# R3-URC18-4-002-002.net
KiCad netlist of a schematic drawn in EAGLE
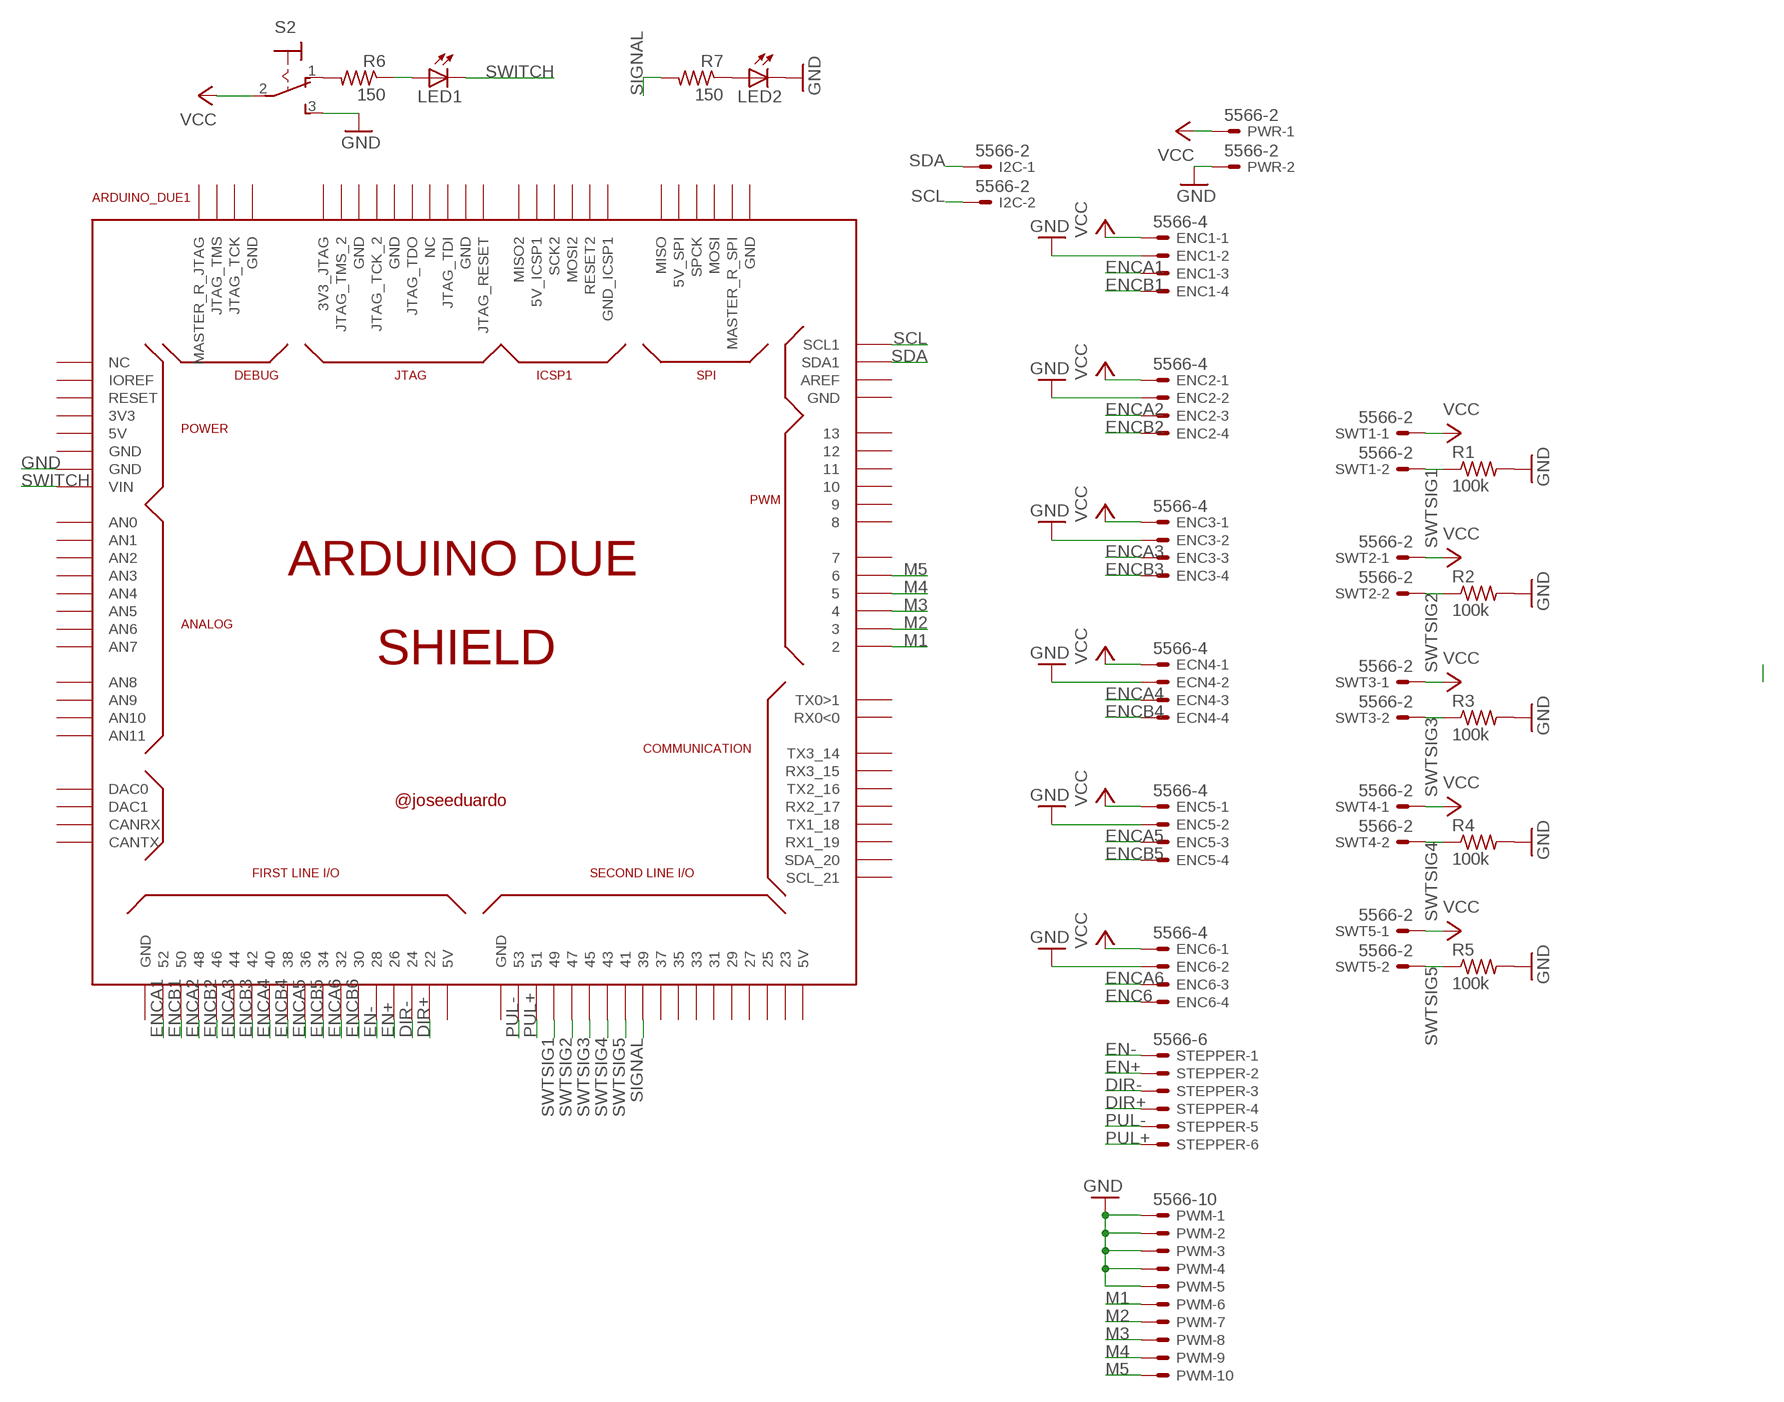
[diagram p0: schematic, sheet 1]

(export (version "E")
  (design (tool "Eeschema 10.0.6"))
  (components
    (comp (ref "ARDUINO_DUE1")
      (value "ARDUINO_DUE_SHIELD")
      (footprint "eagle-import:ARDUINO_DUE_SHIELD")
      (libsource (lib "eagle-import") (part "ARDUINO_DUE_SHIELD"))
    )
    (comp (ref "ECN4")
      (value "5566-4")
      (footprint "eagle-import:5566-4")
      (libsource (lib "eagle-import") (part "5566-4"))
    )
    (comp (ref "ENC1")
      (value "5566-4")
      (footprint "eagle-import:5566-4")
      (libsource (lib "eagle-import") (part "5566-4"))
    )
    (comp (ref "ENC2")
      (value "5566-4")
      (footprint "eagle-import:5566-4")
      (libsource (lib "eagle-import") (part "5566-4"))
    )
    (comp (ref "ENC3")
      (value "5566-4")
      (footprint "eagle-import:5566-4")
      (libsource (lib "eagle-import") (part "5566-4"))
    )
    (comp (ref "ENC5")
      (value "5566-4")
      (footprint "eagle-import:5566-4")
      (libsource (lib "eagle-import") (part "5566-4"))
    )
    (comp (ref "ENC6")
      (value "5566-4")
      (footprint "eagle-import:5566-4")
      (libsource (lib "eagle-import") (part "5566-4"))
    )
    (comp (ref "I2C")
      (value "5566-2")
      (footprint "eagle-import:5566-2")
      (libsource (lib "eagle-import") (part "5566-2"))
    )
    (comp (ref "LED1")
      (value "LED5MM")
      (footprint "eagle-import:LED5MM")
      (libsource (lib "eagle-import") (part "LED5MM"))
    )
    (comp (ref "LED2")
      (value "LED5MM")
      (footprint "eagle-import:LED5MM")
      (libsource (lib "eagle-import") (part "LED5MM"))
    )
    (comp (ref "PWM")
      (value "5566-10")
      (footprint "eagle-import:5566-10")
      (libsource (lib "eagle-import") (part "5566-10"))
    )
    (comp (ref "PWR")
      (value "5566-2")
      (footprint "eagle-import:5566-2")
      (libsource (lib "eagle-import") (part "5566-2"))
    )
    (comp (ref "R1")
      (value "100k")
      (footprint "eagle-import:0207_10")
      (libsource (lib "eagle-import") (part "R-US_0207/10"))
    )
    (comp (ref "R2")
      (value "100k")
      (footprint "eagle-import:0207_10")
      (libsource (lib "eagle-import") (part "R-US_0207/10"))
    )
    (comp (ref "R3")
      (value "100k")
      (footprint "eagle-import:0207_10")
      (libsource (lib "eagle-import") (part "R-US_0207/10"))
    )
    (comp (ref "R4")
      (value "100k")
      (footprint "eagle-import:0207_10")
      (libsource (lib "eagle-import") (part "R-US_0207/10"))
    )
    (comp (ref "R5")
      (value "100k")
      (footprint "eagle-import:0207_10")
      (libsource (lib "eagle-import") (part "R-US_0207/10"))
    )
    (comp (ref "R6")
      (value "150")
      (footprint "eagle-import:0207_10")
      (libsource (lib "eagle-import") (part "R-US_0207/10"))
    )
    (comp (ref "R7")
      (value "150")
      (footprint "eagle-import:0207_10")
      (libsource (lib "eagle-import") (part "R-US_0207/10"))
    )
    (comp (ref "S2")
      (value "M9040P")
      (footprint "eagle-import:M9040P")
      (libsource (lib "eagle-import") (part "M9040P"))
    )
    (comp (ref "STEPPER")
      (value "5566-6")
      (footprint "eagle-import:5566-6")
      (fields (field (name "MPN") "95566-61002"))
      (libsource (lib "eagle-import") (part "5566-6"))
    )
    (comp (ref "SWT1")
      (value "5566-2")
      (footprint "eagle-import:5566-2")
      (libsource (lib "eagle-import") (part "5566-2"))
    )
    (comp (ref "SWT2")
      (value "5566-2")
      (footprint "eagle-import:5566-2")
      (libsource (lib "eagle-import") (part "5566-2"))
    )
    (comp (ref "SWT3")
      (value "5566-2")
      (footprint "eagle-import:5566-2")
      (libsource (lib "eagle-import") (part "5566-2"))
    )
    (comp (ref "SWT4")
      (value "5566-2")
      (footprint "eagle-import:5566-2")
      (libsource (lib "eagle-import") (part "5566-2"))
    )
    (comp (ref "SWT5")
      (value "5566-2")
      (footprint "eagle-import:5566-2")
      (libsource (lib "eagle-import") (part "5566-2"))
    )
  )
  (nets
    (net (code "1") (name "/DIR+") (class "Default")
      (node (ref "ARDUINO_DUE1") (pin "22") (pinfunction "22_22") (pintype "bidirectional"))
      (node (ref "STEPPER") (pin "4") (pinfunction "S_4") (pintype "passive"))
    )
    (net (code "2") (name "/DIR-") (class "Default")
      (node (ref "ARDUINO_DUE1") (pin "24") (pinfunction "24_24") (pintype "bidirectional"))
      (node (ref "STEPPER") (pin "3") (pinfunction "S_3") (pintype "passive"))
    )
    (net (code "3") (name "/EN+") (class "Default")
      (node (ref "ARDUINO_DUE1") (pin "26") (pinfunction "26_26") (pintype "bidirectional"))
      (node (ref "STEPPER") (pin "2") (pinfunction "S_2") (pintype "passive"))
    )
    (net (code "4") (name "/EN-") (class "Default")
      (node (ref "ARDUINO_DUE1") (pin "28") (pinfunction "28_28") (pintype "bidirectional"))
      (node (ref "STEPPER") (pin "1") (pinfunction "S_1") (pintype "passive"))
    )
    (net (code "5") (name "/ENC6") (class "Default")
      (node (ref "ENC6") (pin "4") (pinfunction "S_4") (pintype "passive"))
    )
    (net (code "6") (name "/ENCA1") (class "Default")
      (node (ref "ARDUINO_DUE1") (pin "52") (pinfunction "52_52") (pintype "bidirectional"))
      (node (ref "ENC1") (pin "3") (pinfunction "S_3") (pintype "passive"))
    )
    (net (code "7") (name "/ENCA2") (class "Default")
      (node (ref "ARDUINO_DUE1") (pin "48") (pinfunction "48_48") (pintype "bidirectional"))
      (node (ref "ENC2") (pin "3") (pinfunction "S_3") (pintype "passive"))
    )
    (net (code "8") (name "/ENCA3") (class "Default")
      (node (ref "ARDUINO_DUE1") (pin "44") (pinfunction "44_44") (pintype "bidirectional"))
      (node (ref "ENC3") (pin "3") (pinfunction "S_3") (pintype "passive"))
    )
    (net (code "9") (name "/ENCA4") (class "Default")
      (node (ref "ARDUINO_DUE1") (pin "40") (pinfunction "40_40") (pintype "bidirectional"))
      (node (ref "ECN4") (pin "3") (pinfunction "S_3") (pintype "passive"))
    )
    (net (code "10") (name "/ENCA5") (class "Default")
      (node (ref "ARDUINO_DUE1") (pin "36") (pinfunction "36_36") (pintype "bidirectional"))
      (node (ref "ENC5") (pin "3") (pinfunction "S_3") (pintype "passive"))
    )
    (net (code "11") (name "/ENCA6") (class "Default")
      (node (ref "ARDUINO_DUE1") (pin "32") (pinfunction "32_32") (pintype "bidirectional"))
      (node (ref "ENC6") (pin "3") (pinfunction "S_3") (pintype "passive"))
    )
    (net (code "12") (name "/ENCB1") (class "Default")
      (node (ref "ARDUINO_DUE1") (pin "50") (pinfunction "50_50") (pintype "bidirectional"))
      (node (ref "ENC1") (pin "4") (pinfunction "S_4") (pintype "passive"))
    )
    (net (code "13") (name "/ENCB2") (class "Default")
      (node (ref "ARDUINO_DUE1") (pin "46") (pinfunction "46_46") (pintype "bidirectional"))
      (node (ref "ENC2") (pin "4") (pinfunction "S_4") (pintype "passive"))
    )
    (net (code "14") (name "/ENCB3") (class "Default")
      (node (ref "ARDUINO_DUE1") (pin "42") (pinfunction "42_42") (pintype "bidirectional"))
      (node (ref "ENC3") (pin "4") (pinfunction "S_4") (pintype "passive"))
    )
    (net (code "15") (name "/ENCB4") (class "Default")
      (node (ref "ARDUINO_DUE1") (pin "38") (pinfunction "38_38") (pintype "bidirectional"))
      (node (ref "ECN4") (pin "4") (pinfunction "S_4") (pintype "passive"))
    )
    (net (code "16") (name "/ENCB5") (class "Default")
      (node (ref "ARDUINO_DUE1") (pin "34") (pinfunction "34_34") (pintype "bidirectional"))
      (node (ref "ENC5") (pin "4") (pinfunction "S_4") (pintype "passive"))
    )
    (net (code "17") (name "/ENCB6") (class "Default")
      (node (ref "ARDUINO_DUE1") (pin "30") (pinfunction "30_30") (pintype "bidirectional"))
    )
    (net (code "18") (name "/M1") (class "Default")
      (node (ref "ARDUINO_DUE1") (pin "2") (pinfunction "2_2") (pintype "bidirectional"))
      (node (ref "PWM") (pin "6") (pinfunction "S_6") (pintype "passive"))
    )
    (net (code "19") (name "/M2") (class "Default")
      (node (ref "ARDUINO_DUE1") (pin "3") (pinfunction "3_3") (pintype "bidirectional"))
      (node (ref "PWM") (pin "7") (pinfunction "S_7") (pintype "passive"))
    )
    (net (code "20") (name "/M3") (class "Default")
      (node (ref "ARDUINO_DUE1") (pin "4") (pinfunction "4_4") (pintype "bidirectional"))
      (node (ref "PWM") (pin "8") (pinfunction "S_8") (pintype "passive"))
    )
    (net (code "21") (name "/M4") (class "Default")
      (node (ref "ARDUINO_DUE1") (pin "5") (pinfunction "5_5") (pintype "bidirectional"))
      (node (ref "PWM") (pin "9") (pinfunction "S_9") (pintype "passive"))
    )
    (net (code "22") (name "/M5") (class "Default")
      (node (ref "ARDUINO_DUE1") (pin "6") (pinfunction "6_6") (pintype "bidirectional"))
      (node (ref "PWM") (pin "10") (pinfunction "S_10") (pintype "passive"))
    )
    (net (code "23") (name "/PUL+") (class "Default")
      (node (ref "ARDUINO_DUE1") (pin "51") (pinfunction "51_51") (pintype "bidirectional"))
      (node (ref "STEPPER") (pin "6") (pinfunction "S_6") (pintype "passive"))
    )
    (net (code "24") (name "/PUL-") (class "Default")
      (node (ref "ARDUINO_DUE1") (pin "53") (pinfunction "53_53") (pintype "bidirectional"))
      (node (ref "STEPPER") (pin "5") (pinfunction "S_5") (pintype "passive"))
    )
    (net (code "25") (name "/SCL") (class "Default")
      (node (ref "ARDUINO_DUE1") (pin "SCL1") (pinfunction "SCL1_SCL1") (pintype "bidirectional"))
      (node (ref "I2C") (pin "2") (pinfunction "S_2") (pintype "passive"))
    )
    (net (code "26") (name "/SDA") (class "Default")
      (node (ref "ARDUINO_DUE1") (pin "SDA1") (pinfunction "SDA1_SDA1") (pintype "bidirectional"))
      (node (ref "I2C") (pin "1") (pinfunction "S_1") (pintype "passive"))
    )
    (net (code "27") (name "/SIGNAL") (class "Default")
      (node (ref "ARDUINO_DUE1") (pin "39") (pinfunction "39_39") (pintype "bidirectional"))
      (node (ref "R7") (pin "2") (pinfunction "2_2") (pintype "passive"))
    )
    (net (code "28") (name "/SWITCH") (class "Default")
      (node (ref "ARDUINO_DUE1") (pin "VIN") (pinfunction "VIN_VIN") (pintype "bidirectional"))
      (node (ref "LED1") (pin "K") (pinfunction "C_K") (pintype "passive"))
    )
    (net (code "29") (name "/SWTSIG1") (class "Default")
      (node (ref "ARDUINO_DUE1") (pin "49") (pinfunction "49_49") (pintype "bidirectional"))
      (node (ref "R1") (pin "1") (pinfunction "1_1") (pintype "passive"))
      (node (ref "SWT1") (pin "2") (pinfunction "S_2") (pintype "passive"))
    )
    (net (code "30") (name "/SWTSIG2") (class "Default")
      (node (ref "ARDUINO_DUE1") (pin "47") (pinfunction "47_47") (pintype "bidirectional"))
      (node (ref "R2") (pin "1") (pinfunction "1_1") (pintype "passive"))
      (node (ref "SWT2") (pin "2") (pinfunction "S_2") (pintype "passive"))
    )
    (net (code "31") (name "/SWTSIG3") (class "Default")
      (node (ref "ARDUINO_DUE1") (pin "45") (pinfunction "45_45") (pintype "bidirectional"))
      (node (ref "R3") (pin "1") (pinfunction "1_1") (pintype "passive"))
      (node (ref "SWT3") (pin "2") (pinfunction "S_2") (pintype "passive"))
    )
    (net (code "32") (name "/SWTSIG4") (class "Default")
      (node (ref "ARDUINO_DUE1") (pin "43") (pinfunction "43_43") (pintype "bidirectional"))
      (node (ref "R4") (pin "1") (pinfunction "1_1") (pintype "passive"))
      (node (ref "SWT4") (pin "2") (pinfunction "S_2") (pintype "passive"))
    )
    (net (code "33") (name "/SWTSIG5") (class "Default")
      (node (ref "ARDUINO_DUE1") (pin "41") (pinfunction "41_41") (pintype "bidirectional"))
      (node (ref "R5") (pin "1") (pinfunction "1_1") (pintype "passive"))
      (node (ref "SWT5") (pin "2") (pinfunction "S_2") (pintype "passive"))
    )
    (net (code "34") (name "GND") (class "Default")
      (node (ref "ARDUINO_DUE1") (pin "GND_1") (pinfunction "GND_GND_1") (pintype "bidirectional"))
      (node (ref "ECN4") (pin "2") (pinfunction "S_2") (pintype "passive"))
      (node (ref "ENC1") (pin "2") (pinfunction "S_2") (pintype "passive"))
      (node (ref "ENC2") (pin "2") (pinfunction "S_2") (pintype "passive"))
      (node (ref "ENC3") (pin "2") (pinfunction "S_2") (pintype "passive"))
      (node (ref "ENC5") (pin "2") (pinfunction "S_2") (pintype "passive"))
      (node (ref "ENC6") (pin "2") (pinfunction "S_2") (pintype "passive"))
      (node (ref "LED2") (pin "K") (pinfunction "C_K") (pintype "passive"))
      (node (ref "PWM") (pin "1") (pinfunction "S_1") (pintype "passive"))
      (node (ref "PWM") (pin "2") (pinfunction "S_2") (pintype "passive"))
      (node (ref "PWM") (pin "3") (pinfunction "S_3") (pintype "passive"))
      (node (ref "PWM") (pin "4") (pinfunction "S_4") (pintype "passive"))
      (node (ref "PWM") (pin "5") (pinfunction "S_5") (pintype "passive"))
      (node (ref "PWR") (pin "2") (pinfunction "S_2") (pintype "passive"))
      (node (ref "R1") (pin "2") (pinfunction "2_2") (pintype "passive"))
      (node (ref "R2") (pin "2") (pinfunction "2_2") (pintype "passive"))
      (node (ref "R3") (pin "2") (pinfunction "2_2") (pintype "passive"))
      (node (ref "R4") (pin "2") (pinfunction "2_2") (pintype "passive"))
      (node (ref "R5") (pin "2") (pinfunction "2_2") (pintype "passive"))
      (node (ref "S2") (pin "3") (pinfunction "S_3") (pintype "passive"))
    )
    (net (code "35") (name "Net-(LED1-PadA)") (class "Default")
      (node (ref "LED1") (pin "A") (pinfunction "A_A") (pintype "passive"))
      (node (ref "R6") (pin "1") (pinfunction "1_1") (pintype "passive"))
    )
    (net (code "36") (name "Net-(LED2-PadA)") (class "Default")
      (node (ref "LED2") (pin "A") (pinfunction "A_A") (pintype "passive"))
      (node (ref "R7") (pin "1") (pinfunction "1_1") (pintype "passive"))
    )
    (net (code "37") (name "Net-(S2-O)") (class "Default")
      (node (ref "R6") (pin "2") (pinfunction "2_2") (pintype "passive"))
      (node (ref "S2") (pin "1") (pinfunction "O_1") (pintype "passive"))
    )
    (net (code "38") (name "VCC") (class "Default")
      (node (ref "ECN4") (pin "1") (pinfunction "S_1") (pintype "passive"))
      (node (ref "ENC1") (pin "1") (pinfunction "S_1") (pintype "passive"))
      (node (ref "ENC2") (pin "1") (pinfunction "S_1") (pintype "passive"))
      (node (ref "ENC3") (pin "1") (pinfunction "S_1") (pintype "passive"))
      (node (ref "ENC5") (pin "1") (pinfunction "S_1") (pintype "passive"))
      (node (ref "ENC6") (pin "1") (pinfunction "S_1") (pintype "passive"))
      (node (ref "PWR") (pin "1") (pinfunction "S_1") (pintype "passive"))
      (node (ref "S2") (pin "2") (pinfunction "P_2") (pintype "passive"))
      (node (ref "SWT1") (pin "1") (pinfunction "S_1") (pintype "passive"))
      (node (ref "SWT2") (pin "1") (pinfunction "S_1") (pintype "passive"))
      (node (ref "SWT3") (pin "1") (pinfunction "S_1") (pintype "passive"))
      (node (ref "SWT4") (pin "1") (pinfunction "S_1") (pintype "passive"))
      (node (ref "SWT5") (pin "1") (pinfunction "S_1") (pintype "passive"))
    )
    (net (code "39") (name "unconnected-(ARDUINO_DUE1-5V-Pad5V0)") (class "Default")
      (node (ref "ARDUINO_DUE1") (pin "5V0") (pinfunction "5V_5V0") (pintype "bidirectional"))
    )
    (net (code "40") (name "unconnected-(ARDUINO_DUE1-5V-Pad5V0_1)") (class "Default")
      (node (ref "ARDUINO_DUE1") (pin "5V0_1") (pinfunction "5V_5V0_1") (pintype "bidirectional"))
    )
    (net (code "41") (name "unconnected-(ARDUINO_DUE1-5V-Pad5V0_2)") (class "Default")
      (node (ref "ARDUINO_DUE1") (pin "5V0_2") (pinfunction "5V_5V0_2") (pintype "bidirectional"))
    )
    (net (code "42") (name "unconnected-(ARDUINO_DUE1-5V_SPI-Pad5V_2)") (class "Default")
      (node (ref "ARDUINO_DUE1") (pin "5V_2") (pinfunction "5V_SPI_5V_2") (pintype "bidirectional"))
    )
    (net (code "43") (name "unconnected-(ARDUINO_DUE1-AN0-PadA0)") (class "Default")
      (node (ref "ARDUINO_DUE1") (pin "A0") (pinfunction "AN0_A0") (pintype "bidirectional"))
    )
    (net (code "44") (name "unconnected-(ARDUINO_DUE1-AN1-PadA1)") (class "Default")
      (node (ref "ARDUINO_DUE1") (pin "A1") (pinfunction "AN1_A1") (pintype "bidirectional"))
    )
    (net (code "45") (name "unconnected-(ARDUINO_DUE1-AN2-PadA2)") (class "Default")
      (node (ref "ARDUINO_DUE1") (pin "A2") (pinfunction "AN2_A2") (pintype "bidirectional"))
    )
    (net (code "46") (name "unconnected-(ARDUINO_DUE1-AN3-PadA3)") (class "Default")
      (node (ref "ARDUINO_DUE1") (pin "A3") (pinfunction "AN3_A3") (pintype "bidirectional"))
    )
    (net (code "47") (name "unconnected-(ARDUINO_DUE1-AN4-PadA4)") (class "Default")
      (node (ref "ARDUINO_DUE1") (pin "A4") (pinfunction "AN4_A4") (pintype "bidirectional"))
    )
    (net (code "48") (name "unconnected-(ARDUINO_DUE1-AN5-PadA5)") (class "Default")
      (node (ref "ARDUINO_DUE1") (pin "A5") (pinfunction "AN5_A5") (pintype "bidirectional"))
    )
    (net (code "49") (name "unconnected-(ARDUINO_DUE1-AN6-PadA6)") (class "Default")
      (node (ref "ARDUINO_DUE1") (pin "A6") (pinfunction "AN6_A6") (pintype "bidirectional"))
    )
    (net (code "50") (name "unconnected-(ARDUINO_DUE1-AN7-PadA7)") (class "Default")
      (node (ref "ARDUINO_DUE1") (pin "A7") (pinfunction "AN7_A7") (pintype "bidirectional"))
    )
    (net (code "51") (name "unconnected-(ARDUINO_DUE1-AN8-PadA8)") (class "Default")
      (node (ref "ARDUINO_DUE1") (pin "A8") (pinfunction "AN8_A8") (pintype "bidirectional"))
    )
    (net (code "52") (name "unconnected-(ARDUINO_DUE1-AN9-PadA9)") (class "Default")
      (node (ref "ARDUINO_DUE1") (pin "A9") (pinfunction "AN9_A9") (pintype "bidirectional"))
    )
    (net (code "53") (name "unconnected-(ARDUINO_DUE1-AN10-PadA10)") (class "Default")
      (node (ref "ARDUINO_DUE1") (pin "A10") (pinfunction "AN10_A10") (pintype "bidirectional"))
    )
    (net (code "54") (name "unconnected-(ARDUINO_DUE1-AN11-PadA11)") (class "Default")
      (node (ref "ARDUINO_DUE1") (pin "A11") (pinfunction "AN11_A11") (pintype "bidirectional"))
    )
    (net (code "55") (name "unconnected-(ARDUINO_DUE1-GND-PadGND_2)") (class "Default")
      (node (ref "ARDUINO_DUE1") (pin "GND_2") (pinfunction "GND_GND_2") (pintype "bidirectional"))
    )
    (net (code "56") (name "unconnected-(ARDUINO_DUE1-GND-PadGND_3)") (class "Default")
      (node (ref "ARDUINO_DUE1") (pin "GND_3") (pinfunction "GND_GND_3") (pintype "bidirectional"))
    )
    (net (code "57") (name "unconnected-(ARDUINO_DUE1-GND-PadGND_4)") (class "Default")
      (node (ref "ARDUINO_DUE1") (pin "GND_4") (pinfunction "GND_GND_4") (pintype "bidirectional"))
    )
    (net (code "58") (name "unconnected-(ARDUINO_DUE1-GND-PadGND_5)") (class "Default")
      (node (ref "ARDUINO_DUE1") (pin "GND_5") (pinfunction "GND_GND_5") (pintype "bidirectional"))
    )
    (net (code "59") (name "unconnected-(ARDUINO_DUE1-GND-PadGND_7)") (class "Default")
      (node (ref "ARDUINO_DUE1") (pin "GND_7") (pinfunction "GND_GND_7") (pintype "bidirectional"))
    )
    (net (code "60") (name "unconnected-(ARDUINO_DUE1-GND-PadGND_8)") (class "Default")
      (node (ref "ARDUINO_DUE1") (pin "GND_8") (pinfunction "GND_GND_8") (pintype "bidirectional"))
    )
    (net (code "61") (name "unconnected-(ARDUINO_DUE1-GND-PadGND_9)") (class "Default")
      (node (ref "ARDUINO_DUE1") (pin "GND_9") (pinfunction "GND_GND_9") (pintype "bidirectional"))
    )
    (net (code "62") (name "unconnected-(ARDUINO_DUE1-GND-PadGND_10)") (class "Default")
      (node (ref "ARDUINO_DUE1") (pin "GND_10") (pinfunction "GND_GND_10") (pintype "bidirectional"))
    )
    (net (code "63") (name "unconnected-(ARDUINO_DUE1-MASTER_R_JTAG-PadMASTER_RESET_JTAG)") (class "Default")
      (node (ref "ARDUINO_DUE1") (pin "MASTER_RESET_JTAG") (pinfunction "MASTER_R_JTAG_MASTER_RESET_JTAG") (pintype "bidirectional"))
    )
    (net (code "64") (name "unconnected-(ARDUINO_DUE1-MASTER_R_SPI-PadMASTER_RESET_SPI)") (class "Default")
      (node (ref "ARDUINO_DUE1") (pin "MASTER_RESET_SPI") (pinfunction "MASTER_R_SPI_MASTER_RESET_SPI") (pintype "bidirectional"))
    )
    (net (code "65") (name "unconnected-(ARDUINO_DUE1-NC-PadNC_2)") (class "Default")
      (node (ref "ARDUINO_DUE1") (pin "NC_2") (pinfunction "NC_NC_2") (pintype "no_connect"))
    )
    (net (code "66") (name "unconnected-(ARDUINO_DUE1-NC-PadNC_5)") (class "Default")
      (node (ref "ARDUINO_DUE1") (pin "NC_5") (pinfunction "NC_NC_5") (pintype "bidirectional"))
    )
    (net (code "67") (name "unconnected-(ARDUINO_DUE1-Pad3V3)") (class "Default")
      (node (ref "ARDUINO_DUE1") (pin "3V3") (pinfunction "3V3_3V3") (pintype "bidirectional"))
    )
    (net (code "68") (name "unconnected-(ARDUINO_DUE1-Pad3V3_JTAG)") (class "Default")
      (node (ref "ARDUINO_DUE1") (pin "3V3_JTAG") (pinfunction "3V3_JTAG_3V3_JTAG") (pintype "bidirectional"))
    )
    (net (code "69") (name "unconnected-(ARDUINO_DUE1-Pad5V_ICSP1)") (class "Default")
      (node (ref "ARDUINO_DUE1") (pin "5V_ICSP1") (pinfunction "5V_ICSP1_5V_ICSP1") (pintype "bidirectional"))
    )
    (net (code "70") (name "unconnected-(ARDUINO_DUE1-Pad7)") (class "Default")
      (node (ref "ARDUINO_DUE1") (pin "7") (pinfunction "7_7") (pintype "bidirectional"))
    )
    (net (code "71") (name "unconnected-(ARDUINO_DUE1-Pad8)") (class "Default")
      (node (ref "ARDUINO_DUE1") (pin "8") (pinfunction "8_8") (pintype "bidirectional"))
    )
    (net (code "72") (name "unconnected-(ARDUINO_DUE1-Pad9)") (class "Default")
      (node (ref "ARDUINO_DUE1") (pin "9") (pinfunction "9_9") (pintype "bidirectional"))
    )
    (net (code "73") (name "unconnected-(ARDUINO_DUE1-Pad10)") (class "Default")
      (node (ref "ARDUINO_DUE1") (pin "10") (pinfunction "10_10") (pintype "bidirectional"))
    )
    (net (code "74") (name "unconnected-(ARDUINO_DUE1-Pad11)") (class "Default")
      (node (ref "ARDUINO_DUE1") (pin "11") (pinfunction "11_11") (pintype "bidirectional"))
    )
    (net (code "75") (name "unconnected-(ARDUINO_DUE1-Pad12)") (class "Default")
      (node (ref "ARDUINO_DUE1") (pin "12") (pinfunction "12_12") (pintype "bidirectional"))
    )
    (net (code "76") (name "unconnected-(ARDUINO_DUE1-Pad13)") (class "Default")
      (node (ref "ARDUINO_DUE1") (pin "13") (pinfunction "13_13") (pintype "bidirectional"))
    )
    (net (code "77") (name "unconnected-(ARDUINO_DUE1-Pad23)") (class "Default")
      (node (ref "ARDUINO_DUE1") (pin "23") (pinfunction "23_23") (pintype "bidirectional"))
    )
    (net (code "78") (name "unconnected-(ARDUINO_DUE1-Pad25)") (class "Default")
      (node (ref "ARDUINO_DUE1") (pin "25") (pinfunction "25_25") (pintype "bidirectional"))
    )
    (net (code "79") (name "unconnected-(ARDUINO_DUE1-Pad27)") (class "Default")
      (node (ref "ARDUINO_DUE1") (pin "27") (pinfunction "27_27") (pintype "bidirectional"))
    )
    (net (code "80") (name "unconnected-(ARDUINO_DUE1-Pad29)") (class "Default")
      (node (ref "ARDUINO_DUE1") (pin "29") (pinfunction "29_29") (pintype "bidirectional"))
    )
    (net (code "81") (name "unconnected-(ARDUINO_DUE1-Pad31)") (class "Default")
      (node (ref "ARDUINO_DUE1") (pin "31") (pinfunction "31_31") (pintype "bidirectional"))
    )
    (net (code "82") (name "unconnected-(ARDUINO_DUE1-Pad33)") (class "Default")
      (node (ref "ARDUINO_DUE1") (pin "33") (pinfunction "33_33") (pintype "bidirectional"))
    )
    (net (code "83") (name "unconnected-(ARDUINO_DUE1-Pad35)") (class "Default")
      (node (ref "ARDUINO_DUE1") (pin "35") (pinfunction "35_35") (pintype "bidirectional"))
    )
    (net (code "84") (name "unconnected-(ARDUINO_DUE1-Pad37)") (class "Default")
      (node (ref "ARDUINO_DUE1") (pin "37") (pinfunction "37_37") (pintype "bidirectional"))
    )
    (net (code "85") (name "unconnected-(ARDUINO_DUE1-PadAREF)") (class "Default")
      (node (ref "ARDUINO_DUE1") (pin "AREF") (pinfunction "AREF_AREF") (pintype "bidirectional"))
    )
    (net (code "86") (name "unconnected-(ARDUINO_DUE1-PadCANRX)") (class "Default")
      (node (ref "ARDUINO_DUE1") (pin "CANRX") (pinfunction "CANRX_CANRX") (pintype "bidirectional"))
    )
    (net (code "87") (name "unconnected-(ARDUINO_DUE1-PadCANTX)") (class "Default")
      (node (ref "ARDUINO_DUE1") (pin "CANTX") (pinfunction "CANTX_CANTX") (pintype "bidirectional"))
    )
    (net (code "88") (name "unconnected-(ARDUINO_DUE1-PadDAC0)") (class "Default")
      (node (ref "ARDUINO_DUE1") (pin "DAC0") (pinfunction "DAC0_DAC0") (pintype "bidirectional"))
    )
    (net (code "89") (name "unconnected-(ARDUINO_DUE1-PadDAC1)") (class "Default")
      (node (ref "ARDUINO_DUE1") (pin "DAC1") (pinfunction "DAC1_DAC1") (pintype "bidirectional"))
    )
    (net (code "90") (name "unconnected-(ARDUINO_DUE1-PadGND)") (class "Default")
      (node (ref "ARDUINO_DUE1") (pin "GND") (pinfunction "GND_GND") (pintype "bidirectional"))
    )
    (net (code "91") (name "unconnected-(ARDUINO_DUE1-PadGND_ICSP1)") (class "Default")
      (node (ref "ARDUINO_DUE1") (pin "GND_ICSP1") (pinfunction "GND_ICSP1_GND_ICSP1") (pintype "bidirectional"))
    )
    (net (code "92") (name "unconnected-(ARDUINO_DUE1-PadIOREF)") (class "Default")
      (node (ref "ARDUINO_DUE1") (pin "IOREF") (pinfunction "IOREF_IOREF") (pintype "bidirectional"))
    )
    (net (code "93") (name "unconnected-(ARDUINO_DUE1-PadJTAG_RESET)") (class "Default")
      (node (ref "ARDUINO_DUE1") (pin "JTAG_RESET") (pinfunction "JTAG_RESET_JTAG_RESET") (pintype "bidirectional"))
    )
    (net (code "94") (name "unconnected-(ARDUINO_DUE1-PadJTAG_TCK)") (class "Default")
      (node (ref "ARDUINO_DUE1") (pin "JTAG_TCK") (pinfunction "JTAG_TCK_JTAG_TCK") (pintype "bidirectional"))
    )
    (net (code "95") (name "unconnected-(ARDUINO_DUE1-PadJTAG_TCK_2)") (class "Default")
      (node (ref "ARDUINO_DUE1") (pin "JTAG_TCK_2") (pinfunction "JTAG_TCK_2_JTAG_TCK_2") (pintype "bidirectional"))
    )
    (net (code "96") (name "unconnected-(ARDUINO_DUE1-PadJTAG_TDI)") (class "Default")
      (node (ref "ARDUINO_DUE1") (pin "JTAG_TDI") (pinfunction "JTAG_TDI_JTAG_TDI") (pintype "bidirectional"))
    )
    (net (code "97") (name "unconnected-(ARDUINO_DUE1-PadJTAG_TDO)") (class "Default")
      (node (ref "ARDUINO_DUE1") (pin "JTAG_TDO") (pinfunction "JTAG_TDO_JTAG_TDO") (pintype "bidirectional"))
    )
    (net (code "98") (name "unconnected-(ARDUINO_DUE1-PadJTAG_TMS)") (class "Default")
      (node (ref "ARDUINO_DUE1") (pin "JTAG_TMS") (pinfunction "JTAG_TMS_JTAG_TMS") (pintype "bidirectional"))
    )
    (net (code "99") (name "unconnected-(ARDUINO_DUE1-PadJTAG_TMS_2)") (class "Default")
      (node (ref "ARDUINO_DUE1") (pin "JTAG_TMS_2") (pinfunction "JTAG_TMS_2_JTAG_TMS_2") (pintype "bidirectional"))
    )
    (net (code "100") (name "unconnected-(ARDUINO_DUE1-PadMISO)") (class "Default")
      (node (ref "ARDUINO_DUE1") (pin "MISO") (pinfunction "MISO_MISO") (pintype "bidirectional"))
    )
    (net (code "101") (name "unconnected-(ARDUINO_DUE1-PadMISO2)") (class "Default")
      (node (ref "ARDUINO_DUE1") (pin "MISO2") (pinfunction "MISO2_MISO2") (pintype "bidirectional"))
    )
    (net (code "102") (name "unconnected-(ARDUINO_DUE1-PadMOSI)") (class "Default")
      (node (ref "ARDUINO_DUE1") (pin "MOSI") (pinfunction "MOSI_MOSI") (pintype "bidirectional"))
    )
    (net (code "103") (name "unconnected-(ARDUINO_DUE1-PadMOSI2)") (class "Default")
      (node (ref "ARDUINO_DUE1") (pin "MOSI2") (pinfunction "MOSI2_MOSI2") (pintype "bidirectional"))
    )
    (net (code "104") (name "unconnected-(ARDUINO_DUE1-PadRESET)") (class "Default")
      (node (ref "ARDUINO_DUE1") (pin "RESET") (pinfunction "RESET_RESET") (pintype "bidirectional"))
    )
    (net (code "105") (name "unconnected-(ARDUINO_DUE1-PadRESET2)") (class "Default")
      (node (ref "ARDUINO_DUE1") (pin "RESET2") (pinfunction "RESET2_RESET2") (pintype "bidirectional"))
    )
    (net (code "106") (name "unconnected-(ARDUINO_DUE1-PadSCK2)") (class "Default")
      (node (ref "ARDUINO_DUE1") (pin "SCK2") (pinfunction "SCK2_SCK2") (pintype "bidirectional"))
    )
    (net (code "107") (name "unconnected-(ARDUINO_DUE1-PadSPCK)") (class "Default")
      (node (ref "ARDUINO_DUE1") (pin "SPCK") (pinfunction "SPCK_SPCK") (pintype "bidirectional"))
    )
    (net (code "108") (name "unconnected-(ARDUINO_DUE1-RX0<0-Pad0)") (class "Default")
      (node (ref "ARDUINO_DUE1") (pin "0") (pinfunction "RX0<0_0") (pintype "bidirectional"))
    )
    (net (code "109") (name "unconnected-(ARDUINO_DUE1-RX1_19-Pad19)") (class "Default")
      (node (ref "ARDUINO_DUE1") (pin "19") (pinfunction "RX1_19_19") (pintype "bidirectional"))
    )
    (net (code "110") (name "unconnected-(ARDUINO_DUE1-RX2_17-Pad17)") (class "Default")
      (node (ref "ARDUINO_DUE1") (pin "17") (pinfunction "RX2_17_17") (pintype "bidirectional"))
    )
    (net (code "111") (name "unconnected-(ARDUINO_DUE1-RX3_15-Pad15)") (class "Default")
      (node (ref "ARDUINO_DUE1") (pin "15") (pinfunction "RX3_15_15") (pintype "bidirectional"))
    )
    (net (code "112") (name "unconnected-(ARDUINO_DUE1-SCL_21-Pad21)") (class "Default")
      (node (ref "ARDUINO_DUE1") (pin "21") (pinfunction "SCL_21_21") (pintype "bidirectional"))
    )
    (net (code "113") (name "unconnected-(ARDUINO_DUE1-SDA_20-Pad20)") (class "Default")
      (node (ref "ARDUINO_DUE1") (pin "20") (pinfunction "SDA_20_20") (pintype "bidirectional"))
    )
    (net (code "114") (name "unconnected-(ARDUINO_DUE1-TX0>1-Pad1)") (class "Default")
      (node (ref "ARDUINO_DUE1") (pin "1") (pinfunction "TX0>1_1") (pintype "bidirectional"))
    )
    (net (code "115") (name "unconnected-(ARDUINO_DUE1-TX1_18-Pad18)") (class "Default")
      (node (ref "ARDUINO_DUE1") (pin "18") (pinfunction "TX1_18_18") (pintype "bidirectional"))
    )
    (net (code "116") (name "unconnected-(ARDUINO_DUE1-TX2_16-Pad16)") (class "Default")
      (node (ref "ARDUINO_DUE1") (pin "16") (pinfunction "TX2_16_16") (pintype "bidirectional"))
    )
    (net (code "117") (name "unconnected-(ARDUINO_DUE1-TX3_14-Pad14)") (class "Default")
      (node (ref "ARDUINO_DUE1") (pin "14") (pinfunction "TX3_14_14") (pintype "bidirectional"))
    )
  )
)
